# S01-INTERFACES.net
KiCad netlist of a schematic drawn in Altium Designer
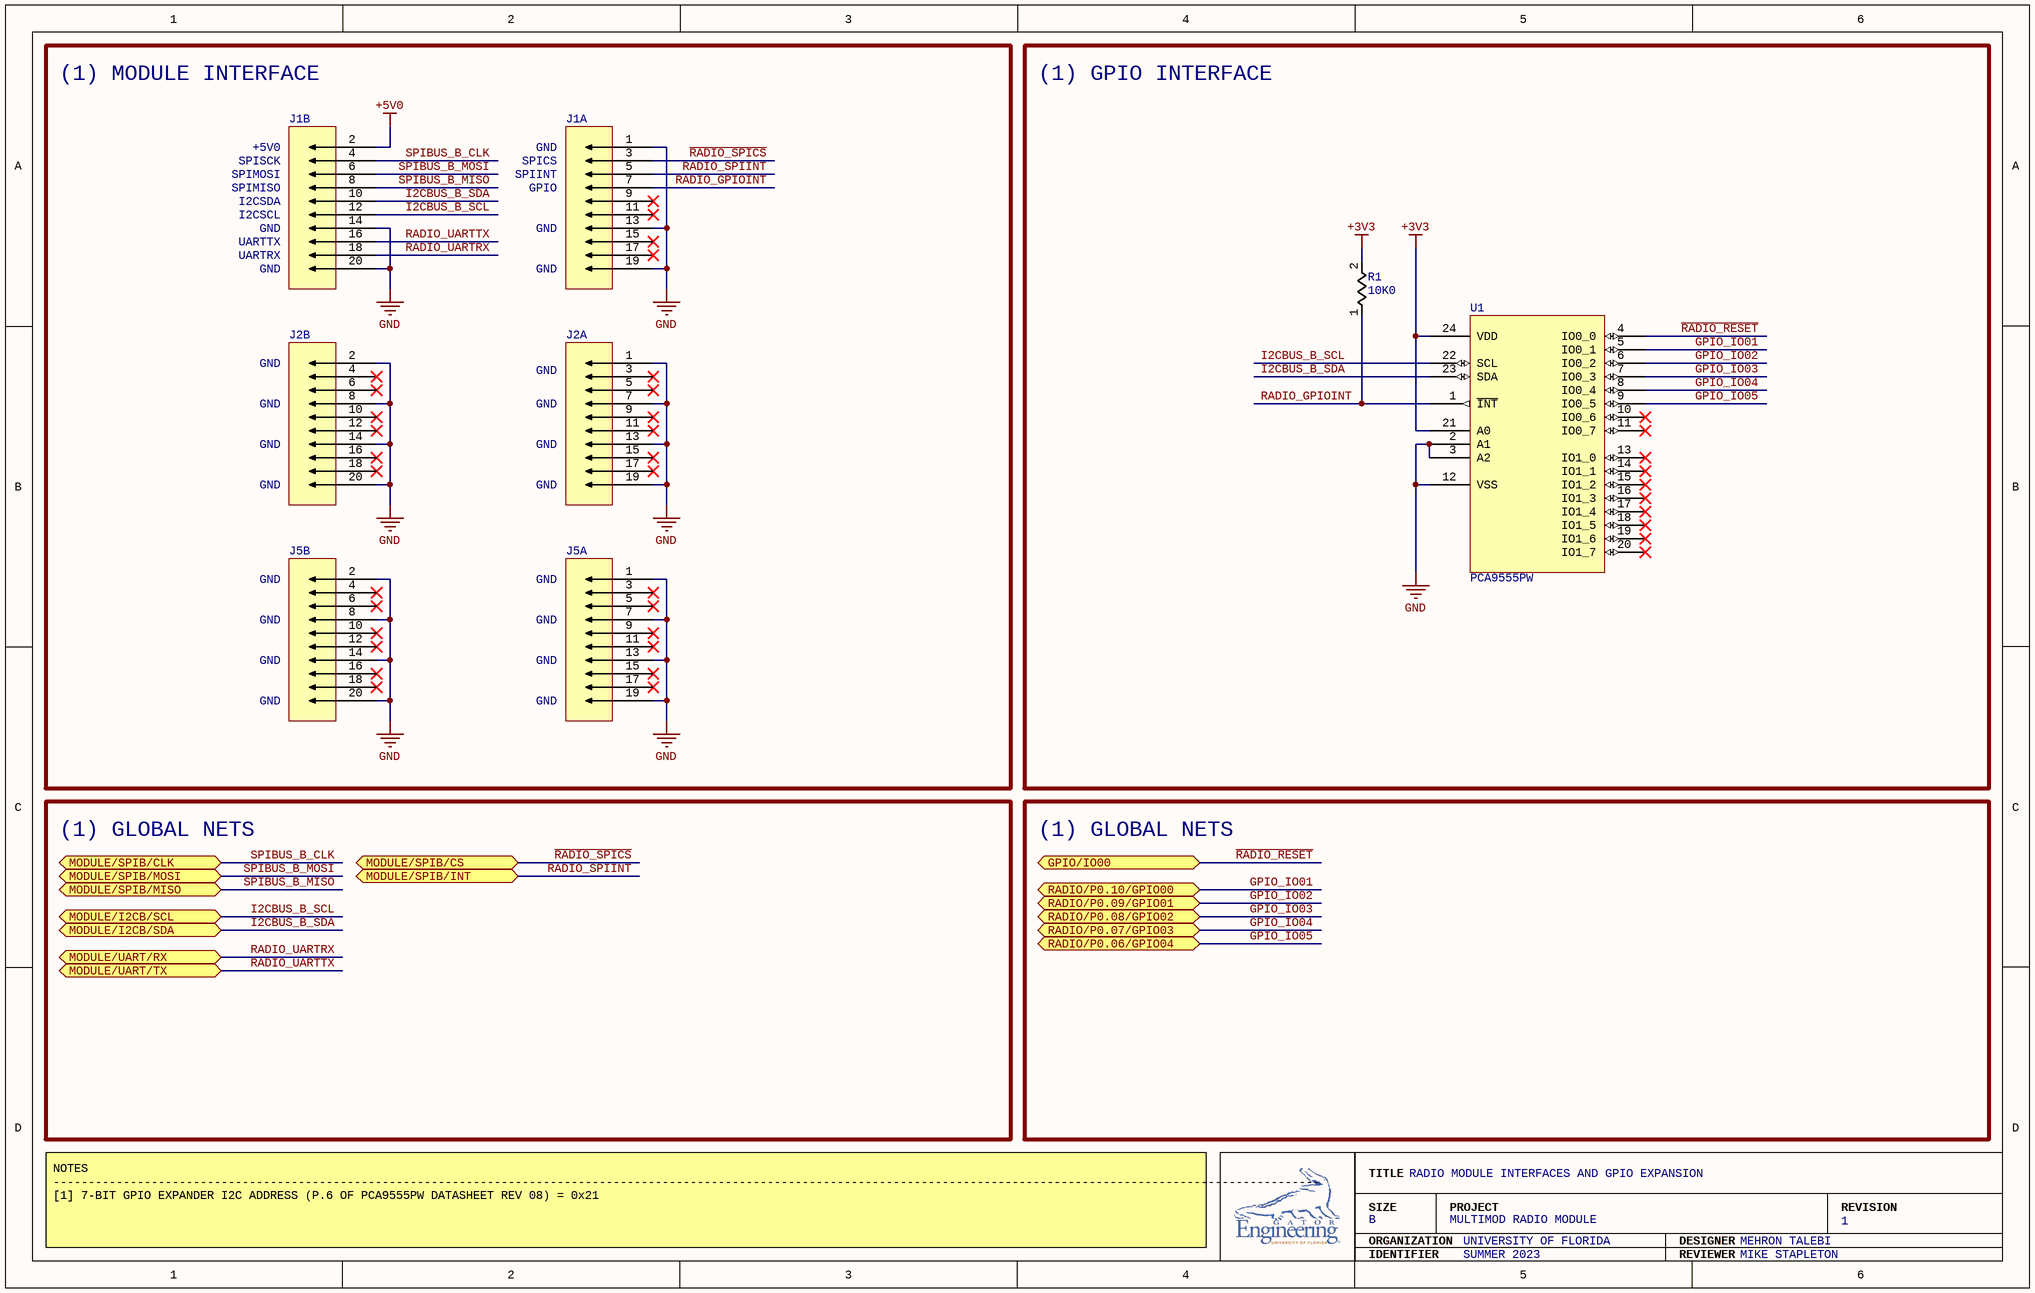
[diagram p0: S01-INTERFACES.SchDoc]

(export (version "E")
  (design (tool "Eeschema 10.0.6"))
  (components
    (comp (ref "J1")
      (value "NPTC102KFMS-RC")
      (footprint "NPTC102KFMS-RC")
      (description "CONN HDR 20POS 0.1 TIN SMD")
      (libsource (lib "Master") (part "NPTC102KFMS-RC"))
    )
    (comp (ref "J2")
      (value "NPTC102KFMS-RC")
      (footprint "NPTC102KFMS-RC")
      (description "CONN HDR 20POS 0.1 TIN SMD")
      (libsource (lib "Master") (part "NPTC102KFMS-RC"))
    )
    (comp (ref "J5")
      (value "NPTC102KFMS-RC")
      (footprint "NPTC102KFMS-RC")
      (description "CONN HDR 20POS 0.1 TIN SMD")
      (libsource (lib "Master") (part "NPTC102KFMS-RC"))
    )
    (comp (ref "R1")
      (value "10K0")
      (footprint "RC0805FR-0710KL")
      (description "RES 10K OHM 1% 1/8W 0805")
      (fields (field (name "TOLERANCE") "±1%"))
      (libsource (lib "Master") (part "RC0805FR-0710KL"))
    )
    (comp (ref "U1")
      (value "PCA9555PW")
      (footprint "PCA9555PW")
      (description "IC XPND 400KHZ I2C SMBUS 24TSSOP")
      (libsource (lib "Master") (part "PCA9555PW"))
    )
  )
  (nets
    (net (code "1") (name "+3V3") (class "Default")
      (node (ref "R1") (pin "2") (pinfunction "2_2") (pintype "passive"))
      (node (ref "U1") (pin "21") (pinfunction "A0_21") (pintype "passive"))
      (node (ref "U1") (pin "24") (pinfunction "VDD_24") (pintype "power_in"))
    )
    (net (code "2") (name "+5V0") (class "Default")
      (node (ref "J1") (pin "2") (pinfunction "2_2") (pintype "passive"))
    )
    (net (code "3") (name "/GPIO_IO01") (class "Default")
      (node (ref "U1") (pin "5") (pinfunction "IO0_1_5") (pintype "bidirectional"))
    )
    (net (code "4") (name "/GPIO_IO02") (class "Default")
      (node (ref "U1") (pin "6") (pinfunction "IO0_2_6") (pintype "bidirectional"))
    )
    (net (code "5") (name "/GPIO_IO03") (class "Default")
      (node (ref "U1") (pin "7") (pinfunction "IO0_3_7") (pintype "bidirectional"))
    )
    (net (code "6") (name "/GPIO_IO04") (class "Default")
      (node (ref "U1") (pin "8") (pinfunction "IO0_4_8") (pintype "bidirectional"))
    )
    (net (code "7") (name "/GPIO_IO05") (class "Default")
      (node (ref "U1") (pin "9") (pinfunction "IO0_5_9") (pintype "bidirectional"))
    )
    (net (code "8") (name "/I2CBUS_B_SCL") (class "Default")
      (node (ref "J1") (pin "12") (pinfunction "12_12") (pintype "passive"))
      (node (ref "U1") (pin "22") (pinfunction "SCL_22") (pintype "bidirectional"))
    )
    (net (code "9") (name "/I2CBUS_B_SDA") (class "Default")
      (node (ref "J1") (pin "10") (pinfunction "10_10") (pintype "passive"))
      (node (ref "U1") (pin "23") (pinfunction "SDA_23") (pintype "bidirectional"))
    )
    (net (code "10") (name "/RADIO_GPIOINT") (class "Default")
      (node (ref "J1") (pin "7") (pinfunction "7_7") (pintype "passive"))
      (node (ref "R1") (pin "1") (pinfunction "1_1") (pintype "passive"))
      (node (ref "U1") (pin "1") (pinfunction "INT_1") (pintype "output"))
    )
    (net (code "11") (name "/RADIO_RESET") (class "Default")
      (node (ref "U1") (pin "4") (pinfunction "IO0_0_4") (pintype "bidirectional"))
    )
    (net (code "12") (name "/RADIO_SPICS") (class "Default")
      (node (ref "J1") (pin "3") (pinfunction "3_3") (pintype "passive"))
    )
    (net (code "13") (name "/RADIO_SPIINT") (class "Default")
      (node (ref "J1") (pin "5") (pinfunction "5_5") (pintype "passive"))
    )
    (net (code "14") (name "/RADIO_UARTRX") (class "Default")
      (node (ref "J1") (pin "18") (pinfunction "18_18") (pintype "passive"))
    )
    (net (code "15") (name "/RADIO_UARTTX") (class "Default")
      (node (ref "J1") (pin "16") (pinfunction "16_16") (pintype "passive"))
    )
    (net (code "16") (name "/SPIBUS_B_CLK") (class "Default")
      (node (ref "J1") (pin "4") (pinfunction "4_4") (pintype "passive"))
    )
    (net (code "17") (name "/SPIBUS_B_MISO") (class "Default")
      (node (ref "J1") (pin "8") (pinfunction "8_8") (pintype "passive"))
    )
    (net (code "18") (name "/SPIBUS_B_MOSI") (class "Default")
      (node (ref "J1") (pin "6") (pinfunction "6_6") (pintype "passive"))
    )
    (net (code "19") (name "GND") (class "Default")
      (node (ref "J1") (pin "1") (pinfunction "1_1") (pintype "passive"))
      (node (ref "J1") (pin "13") (pinfunction "13_13") (pintype "passive"))
      (node (ref "J1") (pin "14") (pinfunction "14_14") (pintype "passive"))
      (node (ref "J1") (pin "19") (pinfunction "19_19") (pintype "passive"))
      (node (ref "J1") (pin "20") (pinfunction "20_20") (pintype "passive"))
      (node (ref "J2") (pin "1") (pinfunction "1_1") (pintype "passive"))
      (node (ref "J2") (pin "13") (pinfunction "13_13") (pintype "passive"))
      (node (ref "J2") (pin "14") (pinfunction "14_14") (pintype "passive"))
      (node (ref "J2") (pin "19") (pinfunction "19_19") (pintype "passive"))
      (node (ref "J2") (pin "2") (pinfunction "2_2") (pintype "passive"))
      (node (ref "J2") (pin "20") (pinfunction "20_20") (pintype "passive"))
      (node (ref "J2") (pin "7") (pinfunction "7_7") (pintype "passive"))
      (node (ref "J2") (pin "8") (pinfunction "8_8") (pintype "passive"))
      (node (ref "J5") (pin "1") (pinfunction "1_1") (pintype "passive"))
      (node (ref "J5") (pin "13") (pinfunction "13_13") (pintype "passive"))
      (node (ref "J5") (pin "14") (pinfunction "14_14") (pintype "passive"))
      (node (ref "J5") (pin "19") (pinfunction "19_19") (pintype "passive"))
      (node (ref "J5") (pin "2") (pinfunction "2_2") (pintype "passive"))
      (node (ref "J5") (pin "20") (pinfunction "20_20") (pintype "passive"))
      (node (ref "J5") (pin "7") (pinfunction "7_7") (pintype "passive"))
      (node (ref "J5") (pin "8") (pinfunction "8_8") (pintype "passive"))
      (node (ref "U1") (pin "12") (pinfunction "VSS_12") (pintype "power_in"))
      (node (ref "U1") (pin "2") (pinfunction "A1_2") (pintype "passive"))
      (node (ref "U1") (pin "3") (pinfunction "A2_3") (pintype "passive"))
    )
    (net (code "20") (name "unconnected-(J1-Pad9)") (class "Default")
      (node (ref "J1") (pin "9") (pinfunction "9_9") (pintype "passive+no_connect"))
    )
    (net (code "21") (name "unconnected-(J1-Pad11)") (class "Default")
      (node (ref "J1") (pin "11") (pinfunction "11_11") (pintype "passive+no_connect"))
    )
    (net (code "22") (name "unconnected-(J1-Pad15)") (class "Default")
      (node (ref "J1") (pin "15") (pinfunction "15_15") (pintype "passive+no_connect"))
    )
    (net (code "23") (name "unconnected-(J1-Pad17)") (class "Default")
      (node (ref "J1") (pin "17") (pinfunction "17_17") (pintype "passive+no_connect"))
    )
    (net (code "24") (name "unconnected-(J2-Pad3)") (class "Default")
      (node (ref "J2") (pin "3") (pinfunction "3_3") (pintype "passive+no_connect"))
    )
    (net (code "25") (name "unconnected-(J2-Pad4)") (class "Default")
      (node (ref "J2") (pin "4") (pinfunction "4_4") (pintype "passive+no_connect"))
    )
    (net (code "26") (name "unconnected-(J2-Pad5)") (class "Default")
      (node (ref "J2") (pin "5") (pinfunction "5_5") (pintype "passive+no_connect"))
    )
    (net (code "27") (name "unconnected-(J2-Pad6)") (class "Default")
      (node (ref "J2") (pin "6") (pinfunction "6_6") (pintype "passive+no_connect"))
    )
    (net (code "28") (name "unconnected-(J2-Pad9)") (class "Default")
      (node (ref "J2") (pin "9") (pinfunction "9_9") (pintype "passive+no_connect"))
    )
    (net (code "29") (name "unconnected-(J2-Pad10)") (class "Default")
      (node (ref "J2") (pin "10") (pinfunction "10_10") (pintype "passive+no_connect"))
    )
    (net (code "30") (name "unconnected-(J2-Pad11)") (class "Default")
      (node (ref "J2") (pin "11") (pinfunction "11_11") (pintype "passive+no_connect"))
    )
    (net (code "31") (name "unconnected-(J2-Pad12)") (class "Default")
      (node (ref "J2") (pin "12") (pinfunction "12_12") (pintype "passive+no_connect"))
    )
    (net (code "32") (name "unconnected-(J2-Pad15)") (class "Default")
      (node (ref "J2") (pin "15") (pinfunction "15_15") (pintype "passive+no_connect"))
    )
    (net (code "33") (name "unconnected-(J2-Pad16)") (class "Default")
      (node (ref "J2") (pin "16") (pinfunction "16_16") (pintype "passive+no_connect"))
    )
    (net (code "34") (name "unconnected-(J2-Pad17)") (class "Default")
      (node (ref "J2") (pin "17") (pinfunction "17_17") (pintype "passive+no_connect"))
    )
    (net (code "35") (name "unconnected-(J2-Pad18)") (class "Default")
      (node (ref "J2") (pin "18") (pinfunction "18_18") (pintype "passive+no_connect"))
    )
    (net (code "36") (name "unconnected-(J5-Pad3)") (class "Default")
      (node (ref "J5") (pin "3") (pinfunction "3_3") (pintype "passive+no_connect"))
    )
    (net (code "37") (name "unconnected-(J5-Pad4)") (class "Default")
      (node (ref "J5") (pin "4") (pinfunction "4_4") (pintype "passive+no_connect"))
    )
    (net (code "38") (name "unconnected-(J5-Pad5)") (class "Default")
      (node (ref "J5") (pin "5") (pinfunction "5_5") (pintype "passive+no_connect"))
    )
    (net (code "39") (name "unconnected-(J5-Pad6)") (class "Default")
      (node (ref "J5") (pin "6") (pinfunction "6_6") (pintype "passive+no_connect"))
    )
    (net (code "40") (name "unconnected-(J5-Pad9)") (class "Default")
      (node (ref "J5") (pin "9") (pinfunction "9_9") (pintype "passive+no_connect"))
    )
    (net (code "41") (name "unconnected-(J5-Pad10)") (class "Default")
      (node (ref "J5") (pin "10") (pinfunction "10_10") (pintype "passive+no_connect"))
    )
    (net (code "42") (name "unconnected-(J5-Pad11)") (class "Default")
      (node (ref "J5") (pin "11") (pinfunction "11_11") (pintype "passive+no_connect"))
    )
    (net (code "43") (name "unconnected-(J5-Pad12)") (class "Default")
      (node (ref "J5") (pin "12") (pinfunction "12_12") (pintype "passive+no_connect"))
    )
    (net (code "44") (name "unconnected-(J5-Pad15)") (class "Default")
      (node (ref "J5") (pin "15") (pinfunction "15_15") (pintype "passive+no_connect"))
    )
    (net (code "45") (name "unconnected-(J5-Pad16)") (class "Default")
      (node (ref "J5") (pin "16") (pinfunction "16_16") (pintype "passive+no_connect"))
    )
    (net (code "46") (name "unconnected-(J5-Pad17)") (class "Default")
      (node (ref "J5") (pin "17") (pinfunction "17_17") (pintype "passive+no_connect"))
    )
    (net (code "47") (name "unconnected-(J5-Pad18)") (class "Default")
      (node (ref "J5") (pin "18") (pinfunction "18_18") (pintype "passive+no_connect"))
    )
    (net (code "48") (name "unconnected-(U1-IO0_6-Pad10)") (class "Default")
      (node (ref "U1") (pin "10") (pinfunction "IO0_6_10") (pintype "bidirectional+no_connect"))
    )
    (net (code "49") (name "unconnected-(U1-IO0_7-Pad11)") (class "Default")
      (node (ref "U1") (pin "11") (pinfunction "IO0_7_11") (pintype "bidirectional+no_connect"))
    )
    (net (code "50") (name "unconnected-(U1-IO1_0-Pad13)") (class "Default")
      (node (ref "U1") (pin "13") (pinfunction "IO1_0_13") (pintype "bidirectional+no_connect"))
    )
    (net (code "51") (name "unconnected-(U1-IO1_1-Pad14)") (class "Default")
      (node (ref "U1") (pin "14") (pinfunction "IO1_1_14") (pintype "bidirectional+no_connect"))
    )
    (net (code "52") (name "unconnected-(U1-IO1_2-Pad15)") (class "Default")
      (node (ref "U1") (pin "15") (pinfunction "IO1_2_15") (pintype "bidirectional+no_connect"))
    )
    (net (code "53") (name "unconnected-(U1-IO1_3-Pad16)") (class "Default")
      (node (ref "U1") (pin "16") (pinfunction "IO1_3_16") (pintype "bidirectional+no_connect"))
    )
    (net (code "54") (name "unconnected-(U1-IO1_4-Pad17)") (class "Default")
      (node (ref "U1") (pin "17") (pinfunction "IO1_4_17") (pintype "bidirectional+no_connect"))
    )
    (net (code "55") (name "unconnected-(U1-IO1_5-Pad18)") (class "Default")
      (node (ref "U1") (pin "18") (pinfunction "IO1_5_18") (pintype "bidirectional+no_connect"))
    )
    (net (code "56") (name "unconnected-(U1-IO1_6-Pad19)") (class "Default")
      (node (ref "U1") (pin "19") (pinfunction "IO1_6_19") (pintype "bidirectional+no_connect"))
    )
    (net (code "57") (name "unconnected-(U1-IO1_7-Pad20)") (class "Default")
      (node (ref "U1") (pin "20") (pinfunction "IO1_7_20") (pintype "bidirectional+no_connect"))
    )
  )
)
